# Sensorboard1.net
KiCad netlist of a schematic drawn in EAGLE
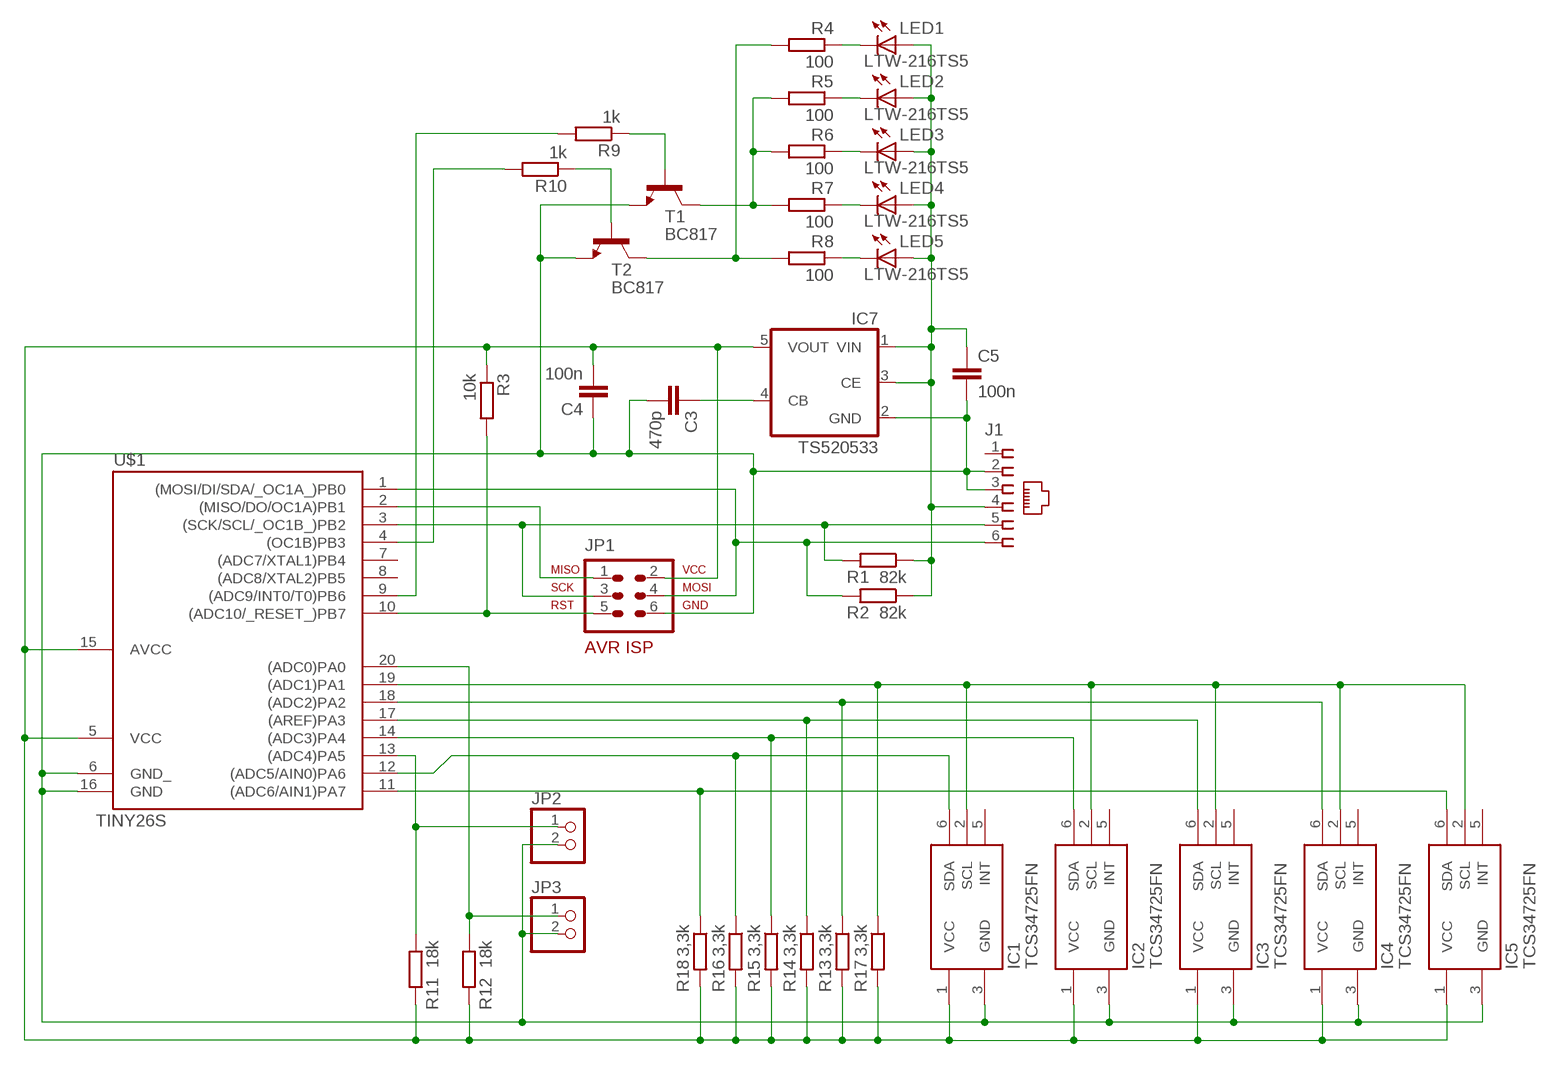
[diagram p0: schematic, sheet 1]

(export (version "E")
  (design (tool "Eeschema 10.0.6"))
  (components
    (comp (ref "C3")
      (value "470p")
      (footprint "eagle-import:C2012")
      (libsource (lib "eagle-import") (part "C-EUC2012"))
    )
    (comp (ref "C4")
      (value "100n")
      (footprint "eagle-import:C2012")
      (libsource (lib "eagle-import") (part "C-EUC2012"))
    )
    (comp (ref "C5")
      (value "100n")
      (footprint "eagle-import:C2012")
      (libsource (lib "eagle-import") (part "C-EUC2012"))
    )
    (comp (ref "IC1")
      (value "TCS34725FN")
      (footprint "eagle-import:DFN-6")
      (libsource (lib "eagle-import") (part "TCS3472FN"))
    )
    (comp (ref "IC2")
      (value "TCS34725FN")
      (footprint "eagle-import:DFN-6")
      (libsource (lib "eagle-import") (part "TCS3472FN"))
    )
    (comp (ref "IC3")
      (value "TCS34725FN")
      (footprint "eagle-import:DFN-6")
      (libsource (lib "eagle-import") (part "TCS3472FN"))
    )
    (comp (ref "IC4")
      (value "TCS34725FN")
      (footprint "eagle-import:DFN-6")
      (libsource (lib "eagle-import") (part "TCS3472FN"))
    )
    (comp (ref "IC5")
      (value "TCS34725FN")
      (footprint "eagle-import:DFN-6")
      (libsource (lib "eagle-import") (part "TCS3472FN"))
    )
    (comp (ref "IC7")
      (value "TS520533")
      (footprint "eagle-import:SOT25")
      (libsource (lib "eagle-import") (part "TS520533"))
    )
    (comp (ref "J1")
      (value "NXT")
      (footprint "eagle-import:NXT")
      (libsource (lib "eagle-import") (part "NXT"))
    )
    (comp (ref "JP1")
      (value "AVR-ISP-6VERT")
      (footprint "eagle-import:AVR-ISP-6")
      (libsource (lib "eagle-import") (part "AVR-ISP-6VERT"))
    )
    (comp (ref "JP2")
      (value "PINHD-1X2")
      (footprint "eagle-import:1X02")
      (libsource (lib "eagle-import") (part "PINHD-1X2"))
    )
    (comp (ref "JP3")
      (value "PINHD-1X2")
      (footprint "eagle-import:1X02")
      (libsource (lib "eagle-import") (part "PINHD-1X2"))
    )
    (comp (ref "LED1")
      (value "LTW-216TS5")
      (footprint "eagle-import:CHIPLED_1206")
      (libsource (lib "eagle-import") (part "LEDCHIPLED_1206"))
    )
    (comp (ref "LED2")
      (value "LTW-216TS5")
      (footprint "eagle-import:CHIPLED_1206")
      (libsource (lib "eagle-import") (part "LEDCHIPLED_1206"))
    )
    (comp (ref "LED3")
      (value "LTW-216TS5")
      (footprint "eagle-import:CHIPLED_1206")
      (libsource (lib "eagle-import") (part "LEDCHIPLED_1206"))
    )
    (comp (ref "LED4")
      (value "LTW-216TS5")
      (footprint "eagle-import:CHIPLED_1206")
      (libsource (lib "eagle-import") (part "LEDCHIPLED_1206"))
    )
    (comp (ref "LED5")
      (value "LTW-216TS5")
      (footprint "eagle-import:CHIPLED_1206")
      (libsource (lib "eagle-import") (part "LEDCHIPLED_1206"))
    )
    (comp (ref "R1")
      (value "82k")
      (footprint "eagle-import:M0805")
      (libsource (lib "eagle-import") (part "R-EU_M0805"))
    )
    (comp (ref "R2")
      (value "82k")
      (footprint "eagle-import:M0805")
      (libsource (lib "eagle-import") (part "R-EU_M0805"))
    )
    (comp (ref "R3")
      (value "10k")
      (footprint "eagle-import:M0805")
      (libsource (lib "eagle-import") (part "R-EU_M0805"))
    )
    (comp (ref "R4")
      (value "100")
      (footprint "eagle-import:M0805")
      (libsource (lib "eagle-import") (part "R-EU_M0805"))
    )
    (comp (ref "R5")
      (value "100")
      (footprint "eagle-import:M0805")
      (libsource (lib "eagle-import") (part "R-EU_M0805"))
    )
    (comp (ref "R6")
      (value "100")
      (footprint "eagle-import:M0805")
      (libsource (lib "eagle-import") (part "R-EU_M0805"))
    )
    (comp (ref "R7")
      (value "100")
      (footprint "eagle-import:M0805")
      (libsource (lib "eagle-import") (part "R-EU_M0805"))
    )
    (comp (ref "R8")
      (value "100")
      (footprint "eagle-import:M0805")
      (libsource (lib "eagle-import") (part "R-EU_M0805"))
    )
    (comp (ref "R9")
      (value "1k")
      (footprint "eagle-import:M0805")
      (libsource (lib "eagle-import") (part "R-EU_M0805"))
    )
    (comp (ref "R10")
      (value "1k")
      (footprint "eagle-import:M0805")
      (libsource (lib "eagle-import") (part "R-EU_M0805"))
    )
    (comp (ref "R11")
      (value "18k")
      (footprint "eagle-import:M0805")
      (libsource (lib "eagle-import") (part "R-EU_M0805"))
    )
    (comp (ref "R12")
      (value "18k")
      (footprint "eagle-import:M0805")
      (libsource (lib "eagle-import") (part "R-EU_M0805"))
    )
    (comp (ref "R13")
      (value "3,3k")
      (footprint "eagle-import:M0805")
      (libsource (lib "eagle-import") (part "R-EU_M0805"))
    )
    (comp (ref "R14")
      (value "3,3k")
      (footprint "eagle-import:M0805")
      (libsource (lib "eagle-import") (part "R-EU_M0805"))
    )
    (comp (ref "R15")
      (value "3,3k")
      (footprint "eagle-import:M0805")
      (libsource (lib "eagle-import") (part "R-EU_M0805"))
    )
    (comp (ref "R16")
      (value "3,3k")
      (footprint "eagle-import:M0805")
      (libsource (lib "eagle-import") (part "R-EU_M0805"))
    )
    (comp (ref "R17")
      (value "3,3k")
      (footprint "eagle-import:M0805")
      (libsource (lib "eagle-import") (part "R-EU_M0805"))
    )
    (comp (ref "R18")
      (value "3,3k")
      (footprint "eagle-import:M0805")
      (libsource (lib "eagle-import") (part "R-EU_M0805"))
    )
    (comp (ref "T1")
      (value "BC817")
      (footprint "eagle-import:SOT23")
      (libsource (lib "eagle-import") (part "BC846"))
    )
    (comp (ref "T2")
      (value "BC817")
      (footprint "eagle-import:SOT23")
      (libsource (lib "eagle-import") (part "BC846"))
    )
    (comp (ref "U$1")
      (value "TINY26S")
      (footprint "eagle-import:SO20L$")
      (libsource (lib "eagle-import") (part "TINY26S"))
    )
  )
  (nets
    (net (code "1") (name "Net-(IC1-GND)") (class "Default")
      (node (ref "C3") (pin "2") (pinfunction "2_2") (pintype "passive"))
      (node (ref "C4") (pin "1") (pinfunction "1_1") (pintype "passive"))
      (node (ref "C5") (pin "2") (pinfunction "2_2") (pintype "passive"))
      (node (ref "IC1") (pin "3") (pinfunction "GND_3") (pintype "power_in"))
      (node (ref "IC2") (pin "3") (pinfunction "GND_3") (pintype "power_in"))
      (node (ref "IC3") (pin "3") (pinfunction "GND_3") (pintype "power_in"))
      (node (ref "IC4") (pin "3") (pinfunction "GND_3") (pintype "power_in"))
      (node (ref "IC5") (pin "3") (pinfunction "GND_3") (pintype "power_in"))
      (node (ref "IC7") (pin "2") (pinfunction "GND_2") (pintype "passive"))
      (node (ref "J1") (pin "2") (pinfunction "2_2") (pintype "passive"))
      (node (ref "J1") (pin "3") (pinfunction "3_3") (pintype "passive"))
      (node (ref "JP1") (pin "6") (pinfunction "6_6") (pintype "passive"))
      (node (ref "JP2") (pin "2") (pinfunction "2_2") (pintype "passive"))
      (node (ref "JP3") (pin "2") (pinfunction "2_2") (pintype "passive"))
      (node (ref "T1") (pin "2") (pinfunction "E_2") (pintype "passive"))
      (node (ref "T2") (pin "2") (pinfunction "E_2") (pintype "passive"))
      (node (ref "U$1") (pin "16") (pinfunction "GND_16") (pintype "power_in"))
      (node (ref "U$1") (pin "6") (pinfunction "GND__6") (pintype "power_in"))
    )
    (net (code "2") (name "Net-(IC1-SCL)") (class "Default")
      (node (ref "IC1") (pin "2") (pinfunction "SCL_2") (pintype "bidirectional"))
      (node (ref "IC2") (pin "2") (pinfunction "SCL_2") (pintype "bidirectional"))
      (node (ref "IC3") (pin "2") (pinfunction "SCL_2") (pintype "bidirectional"))
      (node (ref "IC4") (pin "2") (pinfunction "SCL_2") (pintype "bidirectional"))
      (node (ref "IC5") (pin "2") (pinfunction "SCL_2") (pintype "bidirectional"))
      (node (ref "R17") (pin "1") (pinfunction "1_1") (pintype "passive"))
      (node (ref "U$1") (pin "19") (pinfunction "(ADC1)PA1_19") (pintype "bidirectional"))
    )
    (net (code "3") (name "Net-(IC1-SDA)") (class "Default")
      (node (ref "IC1") (pin "6") (pinfunction "SDA_6") (pintype "bidirectional"))
      (node (ref "R16") (pin "1") (pinfunction "1_1") (pintype "passive"))
      (node (ref "U$1") (pin "12") (pinfunction "(ADC5/AIN0)PA6_12") (pintype "bidirectional"))
    )
    (net (code "4") (name "Net-(IC1-VCC)") (class "Default")
      (node (ref "C4") (pin "2") (pinfunction "2_2") (pintype "passive"))
      (node (ref "IC1") (pin "1") (pinfunction "VCC_1") (pintype "power_in"))
      (node (ref "IC2") (pin "1") (pinfunction "VCC_1") (pintype "power_in"))
      (node (ref "IC3") (pin "1") (pinfunction "VCC_1") (pintype "power_in"))
      (node (ref "IC4") (pin "1") (pinfunction "VCC_1") (pintype "power_in"))
      (node (ref "IC5") (pin "1") (pinfunction "VCC_1") (pintype "power_in"))
      (node (ref "IC7") (pin "5") (pinfunction "VOUT_5") (pintype "passive"))
      (node (ref "JP1") (pin "2") (pinfunction "2_2") (pintype "passive"))
      (node (ref "R11") (pin "2") (pinfunction "2_2") (pintype "passive"))
      (node (ref "R12") (pin "2") (pinfunction "2_2") (pintype "passive"))
      (node (ref "R13") (pin "2") (pinfunction "2_2") (pintype "passive"))
      (node (ref "R14") (pin "2") (pinfunction "2_2") (pintype "passive"))
      (node (ref "R15") (pin "2") (pinfunction "2_2") (pintype "passive"))
      (node (ref "R16") (pin "2") (pinfunction "2_2") (pintype "passive"))
      (node (ref "R17") (pin "2") (pinfunction "2_2") (pintype "passive"))
      (node (ref "R18") (pin "2") (pinfunction "2_2") (pintype "passive"))
      (node (ref "R3") (pin "1") (pinfunction "1_1") (pintype "passive"))
      (node (ref "U$1") (pin "15") (pinfunction "AVCC_15") (pintype "power_in"))
      (node (ref "U$1") (pin "5") (pinfunction "VCC_5") (pintype "power_in"))
    )
    (net (code "5") (name "Net-(IC2-SDA)") (class "Default")
      (node (ref "IC2") (pin "6") (pinfunction "SDA_6") (pintype "bidirectional"))
      (node (ref "R15") (pin "1") (pinfunction "1_1") (pintype "passive"))
      (node (ref "U$1") (pin "14") (pinfunction "(ADC3)PA4_14") (pintype "bidirectional"))
    )
    (net (code "6") (name "Net-(IC3-SDA)") (class "Default")
      (node (ref "IC3") (pin "6") (pinfunction "SDA_6") (pintype "bidirectional"))
      (node (ref "R14") (pin "1") (pinfunction "1_1") (pintype "passive"))
      (node (ref "U$1") (pin "17") (pinfunction "(AREF)PA3_17") (pintype "bidirectional"))
    )
    (net (code "7") (name "Net-(IC4-SDA)") (class "Default")
      (node (ref "IC4") (pin "6") (pinfunction "SDA_6") (pintype "bidirectional"))
      (node (ref "R13") (pin "1") (pinfunction "1_1") (pintype "passive"))
      (node (ref "U$1") (pin "18") (pinfunction "(ADC2)PA2_18") (pintype "bidirectional"))
    )
    (net (code "8") (name "Net-(IC5-SDA)") (class "Default")
      (node (ref "IC5") (pin "6") (pinfunction "SDA_6") (pintype "bidirectional"))
      (node (ref "R18") (pin "1") (pinfunction "1_1") (pintype "passive"))
      (node (ref "U$1") (pin "11") (pinfunction "(ADC6/AIN1)PA7_11") (pintype "bidirectional"))
    )
    (net (code "9") (name "Net-(IC7-CB)") (class "Default")
      (node (ref "C3") (pin "1") (pinfunction "1_1") (pintype "passive"))
      (node (ref "IC7") (pin "4") (pinfunction "CB_4") (pintype "input"))
    )
    (net (code "10") (name "Net-(IC7-CE)") (class "Default")
      (node (ref "C5") (pin "1") (pinfunction "1_1") (pintype "passive"))
      (node (ref "IC7") (pin "1") (pinfunction "VIN_1") (pintype "input"))
      (node (ref "IC7") (pin "3") (pinfunction "CE_3") (pintype "input"))
      (node (ref "J1") (pin "4") (pinfunction "4_4") (pintype "passive"))
      (node (ref "LED1") (pin "A") (pinfunction "A_A") (pintype "passive"))
      (node (ref "LED2") (pin "A") (pinfunction "A_A") (pintype "passive"))
      (node (ref "LED3") (pin "A") (pinfunction "A_A") (pintype "passive"))
      (node (ref "LED4") (pin "A") (pinfunction "A_A") (pintype "passive"))
      (node (ref "LED5") (pin "A") (pinfunction "A_A") (pintype "passive"))
      (node (ref "R1") (pin "1") (pinfunction "1_1") (pintype "passive"))
      (node (ref "R2") (pin "1") (pinfunction "1_1") (pintype "passive"))
    )
    (net (code "11") (name "Net-(LED1-PadC)") (class "Default")
      (node (ref "LED1") (pin "C") (pinfunction "C_C") (pintype "passive"))
      (node (ref "R4") (pin "1") (pinfunction "1_1") (pintype "passive"))
    )
    (net (code "12") (name "Net-(LED2-PadC)") (class "Default")
      (node (ref "LED2") (pin "C") (pinfunction "C_C") (pintype "passive"))
      (node (ref "R5") (pin "1") (pinfunction "1_1") (pintype "passive"))
    )
    (net (code "13") (name "Net-(LED3-PadC)") (class "Default")
      (node (ref "LED3") (pin "C") (pinfunction "C_C") (pintype "passive"))
      (node (ref "R6") (pin "1") (pinfunction "1_1") (pintype "passive"))
    )
    (net (code "14") (name "Net-(LED4-PadC)") (class "Default")
      (node (ref "LED4") (pin "C") (pinfunction "C_C") (pintype "passive"))
      (node (ref "R7") (pin "1") (pinfunction "1_1") (pintype "passive"))
    )
    (net (code "15") (name "Net-(LED5-PadC)") (class "Default")
      (node (ref "LED5") (pin "C") (pinfunction "C_C") (pintype "passive"))
      (node (ref "R8") (pin "1") (pinfunction "1_1") (pintype "passive"))
    )
    (net (code "16") (name "Net-(T1-B)") (class "Default")
      (node (ref "R9") (pin "1") (pinfunction "1_1") (pintype "passive"))
      (node (ref "T1") (pin "1") (pinfunction "B_1") (pintype "passive"))
    )
    (net (code "17") (name "Net-(T1-C)") (class "Default")
      (node (ref "R5") (pin "2") (pinfunction "2_2") (pintype "passive"))
      (node (ref "R6") (pin "2") (pinfunction "2_2") (pintype "passive"))
      (node (ref "R7") (pin "2") (pinfunction "2_2") (pintype "passive"))
      (node (ref "T1") (pin "3") (pinfunction "C_3") (pintype "passive"))
    )
    (net (code "18") (name "Net-(T2-B)") (class "Default")
      (node (ref "R10") (pin "1") (pinfunction "1_1") (pintype "passive"))
      (node (ref "T2") (pin "1") (pinfunction "B_1") (pintype "passive"))
    )
    (net (code "19") (name "Net-(T2-C)") (class "Default")
      (node (ref "R4") (pin "2") (pinfunction "2_2") (pintype "passive"))
      (node (ref "R8") (pin "2") (pinfunction "2_2") (pintype "passive"))
      (node (ref "T2") (pin "3") (pinfunction "C_3") (pintype "passive"))
    )
    (net (code "20") (name "Net-(U$1-(ADC0)PA0)") (class "Default")
      (node (ref "JP3") (pin "1") (pinfunction "1_1") (pintype "passive"))
      (node (ref "R12") (pin "1") (pinfunction "1_1") (pintype "passive"))
      (node (ref "U$1") (pin "20") (pinfunction "(ADC0)PA0_20") (pintype "bidirectional"))
    )
    (net (code "21") (name "Net-(U$1-(ADC4)PA5)") (class "Default")
      (node (ref "JP2") (pin "1") (pinfunction "1_1") (pintype "passive"))
      (node (ref "R11") (pin "1") (pinfunction "1_1") (pintype "passive"))
      (node (ref "U$1") (pin "13") (pinfunction "(ADC4)PA5_13") (pintype "bidirectional"))
    )
    (net (code "22") (name "Net-(U$1-(ADC9{slash}INT0{slash}T0)PB6)") (class "Default")
      (node (ref "R9") (pin "2") (pinfunction "2_2") (pintype "passive"))
      (node (ref "U$1") (pin "9") (pinfunction "(ADC9/INT0/T0)PB6_9") (pintype "bidirectional"))
    )
    (net (code "23") (name "Net-(U$1-(ADC10{slash}_RESET_)PB7)") (class "Default")
      (node (ref "JP1") (pin "5") (pinfunction "5_5") (pintype "passive"))
      (node (ref "R3") (pin "2") (pinfunction "2_2") (pintype "passive"))
      (node (ref "U$1") (pin "10") (pinfunction "(ADC10/_RESET_)PB7_10") (pintype "bidirectional"))
    )
    (net (code "24") (name "Net-(U$1-(MISO{slash}DO{slash}OC1A)PB1)") (class "Default")
      (node (ref "JP1") (pin "1") (pinfunction "1_1") (pintype "passive"))
      (node (ref "U$1") (pin "2") (pinfunction "(MISO/DO/OC1A)PB1_2") (pintype "bidirectional"))
    )
    (net (code "25") (name "Net-(U$1-(MOSI{slash}DI{slash}SDA{slash}_OC1A_)PB0)") (class "Default")
      (node (ref "J1") (pin "6") (pinfunction "6_6") (pintype "passive"))
      (node (ref "JP1") (pin "4") (pinfunction "4_4") (pintype "passive"))
      (node (ref "R2") (pin "2") (pinfunction "2_2") (pintype "passive"))
      (node (ref "U$1") (pin "1") (pinfunction "(MOSI/DI/SDA/_OC1A_)PB0_1") (pintype "bidirectional"))
    )
    (net (code "26") (name "Net-(U$1-(OC1B)PB3)") (class "Default")
      (node (ref "R10") (pin "2") (pinfunction "2_2") (pintype "passive"))
      (node (ref "U$1") (pin "4") (pinfunction "(OC1B)PB3_4") (pintype "bidirectional"))
    )
    (net (code "27") (name "Net-(U$1-(SCK{slash}SCL{slash}_OC1B_)PB2)") (class "Default")
      (node (ref "J1") (pin "5") (pinfunction "5_5") (pintype "passive"))
      (node (ref "JP1") (pin "3") (pinfunction "3_3") (pintype "passive"))
      (node (ref "R1") (pin "2") (pinfunction "2_2") (pintype "passive"))
      (node (ref "U$1") (pin "3") (pinfunction "(SCK/SCL/_OC1B_)PB2_3") (pintype "bidirectional"))
    )
    (net (code "28") (name "unconnected-(IC1-INT-Pad5)") (class "Default")
      (node (ref "IC1") (pin "5") (pinfunction "INT_5") (pintype "output"))
    )
    (net (code "29") (name "unconnected-(IC2-INT-Pad5)") (class "Default")
      (node (ref "IC2") (pin "5") (pinfunction "INT_5") (pintype "output"))
    )
    (net (code "30") (name "unconnected-(IC3-INT-Pad5)") (class "Default")
      (node (ref "IC3") (pin "5") (pinfunction "INT_5") (pintype "output"))
    )
    (net (code "31") (name "unconnected-(IC4-INT-Pad5)") (class "Default")
      (node (ref "IC4") (pin "5") (pinfunction "INT_5") (pintype "output"))
    )
    (net (code "32") (name "unconnected-(IC5-INT-Pad5)") (class "Default")
      (node (ref "IC5") (pin "5") (pinfunction "INT_5") (pintype "output"))
    )
    (net (code "33") (name "unconnected-(J1-Pad1)") (class "Default")
      (node (ref "J1") (pin "1") (pinfunction "1_1") (pintype "passive"))
    )
    (net (code "34") (name "unconnected-(U$1-(ADC7{slash}XTAL1)PB4-Pad7)") (class "Default")
      (node (ref "U$1") (pin "7") (pinfunction "(ADC7/XTAL1)PB4_7") (pintype "bidirectional"))
    )
    (net (code "35") (name "unconnected-(U$1-(ADC8{slash}XTAL2)PB5-Pad8)") (class "Default")
      (node (ref "U$1") (pin "8") (pinfunction "(ADC8/XTAL2)PB5_8") (pintype "bidirectional"))
    )
  )
)
